# POWER_Management.net
KiCad netlist of a schematic drawn in Altium Designer
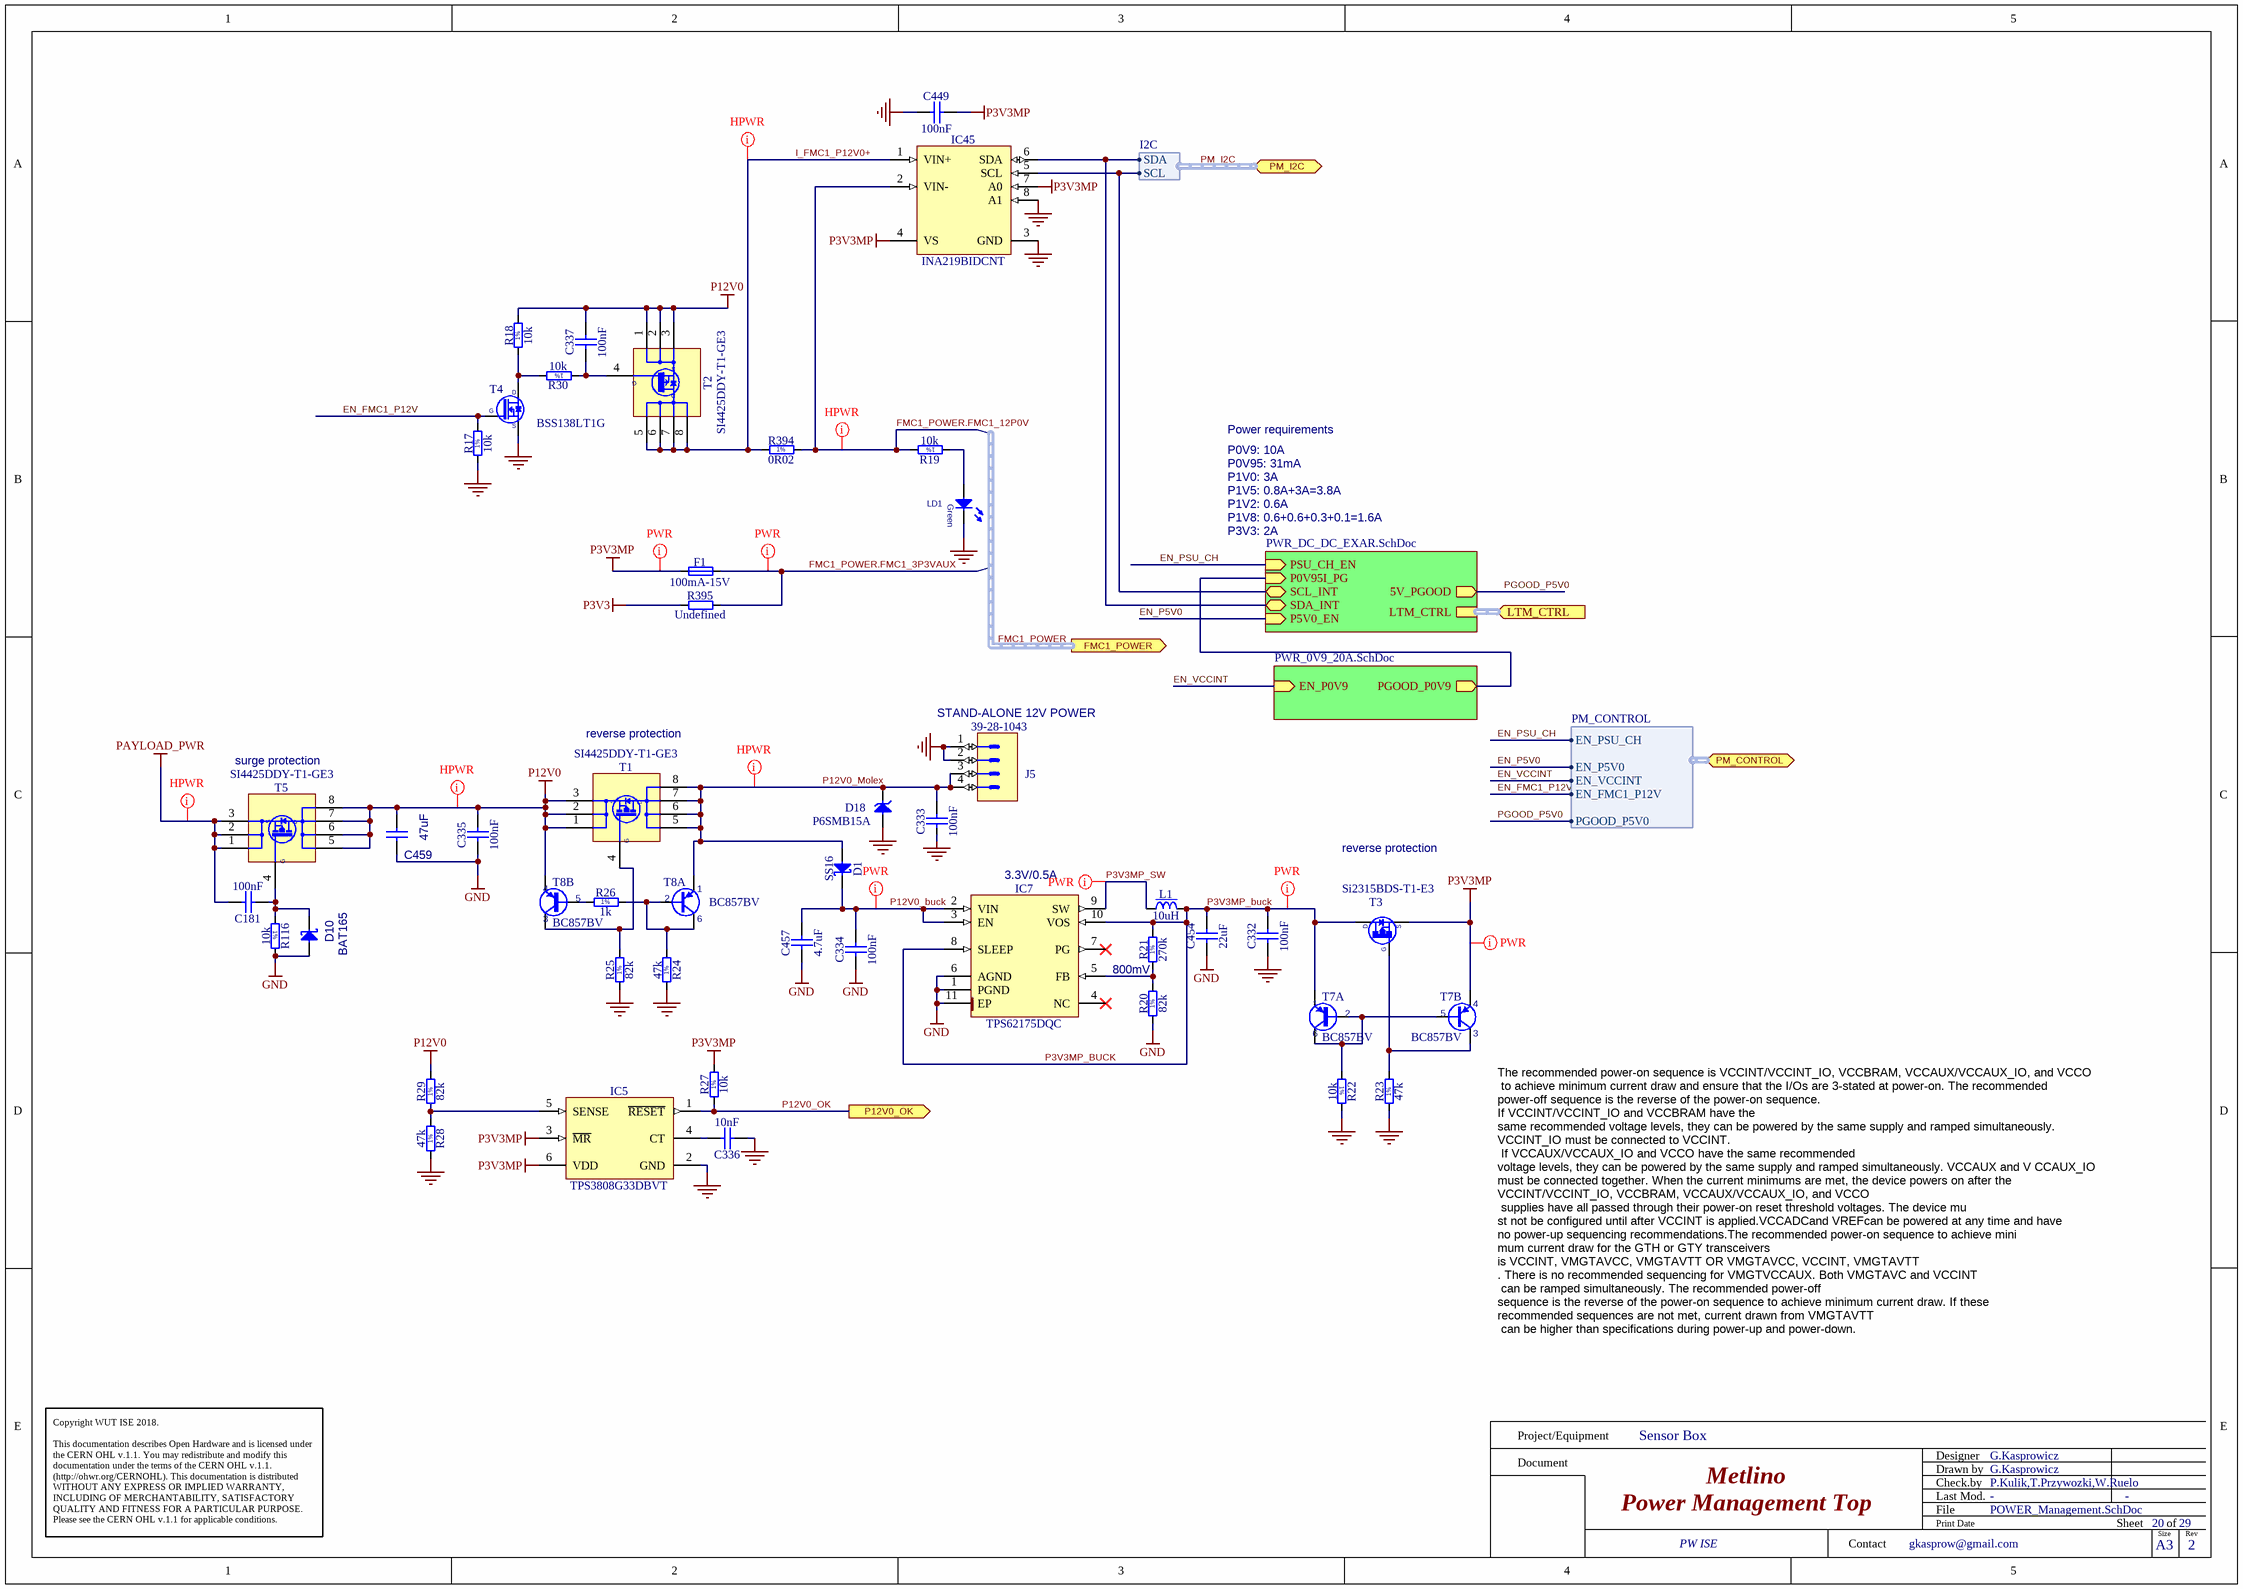
[diagram p0: POWER_Management.SchDoc]

(export (version "E")
  (design (tool "Eeschema 10.0.6"))
  (components
    (comp (ref "C181")
      (value "100nF")
      (footprint "CAPC1005X55N")
      (description "Non-polarised capacitor")
      (fields
        (field (name "MANUFACTURER PART NUMBER") "CC0402_100NF_16V_10%_X5R")
        (field (name "MANUFACTURER") "GENERIC")
        (field (name "AUTHOR") "CERN DEM JLC")
      )
      (libsource (lib "Capacitors") (part "Capacitor - non polarized"))
    )
    (comp (ref "C332")
      (value "100nF")
      (footprint "CAPC1005X55N")
      (description "Non-polarised capacitor")
      (fields
        (field (name "MANUFACTURER PART NUMBER") "CC0402_100NF_16V_10%_X5R")
        (field (name "MANUFACTURER") "GENERIC")
        (field (name "AUTHOR") "CERN DEM JLC")
      )
      (libsource (lib "Capacitors") (part "Capacitor - non polarized"))
    )
    (comp (ref "C333")
      (value "100nF")
      (footprint "CAPC1005X55N")
      (description "Non-polarised capacitor")
      (fields
        (field (name "MANUFACTURER PART NUMBER") "CC0402_100NF_16V_10%_X5R")
        (field (name "MANUFACTURER") "GENERIC")
        (field (name "AUTHOR") "CERN DEM JLC")
      )
      (libsource (lib "Capacitors") (part "Capacitor - non polarized"))
    )
    (comp (ref "C334")
      (value "100nF")
      (footprint "CAPC1005X55N")
      (description "Non-polarised capacitor")
      (fields
        (field (name "MANUFACTURER PART NUMBER") "CC0402_100NF_16V_10%_X5R")
        (field (name "MANUFACTURER") "GENERIC")
        (field (name "AUTHOR") "CERN DEM JLC")
      )
      (libsource (lib "Capacitors") (part "Capacitor - non polarized"))
    )
    (comp (ref "C335")
      (value "100nF")
      (footprint "CAPC1005X55N")
      (description "Non-polarised capacitor")
      (fields
        (field (name "MANUFACTURER PART NUMBER") "CC0402_100NF_16V_10%_X5R")
        (field (name "MANUFACTURER") "GENERIC")
        (field (name "AUTHOR") "CERN DEM JLC")
      )
      (libsource (lib "Capacitors") (part "Capacitor - non polarized"))
    )
    (comp (ref "C336")
      (value "10nF")
      (footprint "CAPC1005X55N")
      (description "Non-polarised capacitor")
      (fields
        (field (name "MANUFACTURER PART NUMBER") "CC0402_10NF_16V_10%_X7R")
        (field (name "MANUFACTURER") "GENERIC")
        (field (name "AUTHOR") "CERN DEM JLC")
      )
      (libsource (lib "Capacitors") (part "Capacitor - non polarized"))
    )
    (comp (ref "C337")
      (value "100nF")
      (footprint "CAPC1005X55N")
      (description "Non-polarised capacitor")
      (fields
        (field (name "MANUFACTURER PART NUMBER") "CC0402_100NF_16V_10%_X5R")
        (field (name "MANUFACTURER") "GENERIC")
        (field (name "AUTHOR") "CERN DEM JLC")
      )
      (libsource (lib "Capacitors") (part "Capacitor - non polarized"))
    )
    (comp (ref "C449")
      (value "100nF")
      (footprint "CAPC1005X55N")
      (description "Non-polarised capacitor")
      (fields
        (field (name "MANUFACTURER PART NUMBER") "CC0402_100NF_16V_10%_X5R")
        (field (name "MANUFACTURER") "GENERIC")
        (field (name "AUTHOR") "CERN DEM JLC")
      )
      (libsource (lib "Capacitors") (part "Capacitor - non polarized"))
    )
    (comp (ref "C454")
      (value "22uF")
      (footprint "CAPC2012X135N")
      (description "Non-polarised capacitor")
      (fields
        (field (name "MANUFACTURER PART NUMBER") "CC0805_22UF_16V_10%_X5R")
        (field (name "MANUFACTURER") "GENERIC")
        (field (name "AUTHOR") "CERN DEM JLC")
      )
      (libsource (lib "Capacitors") (part "Capacitor - non polarized"))
    )
    (comp (ref "C457")
      (value "4.7uF")
      (footprint "CAPC1709X95N")
      (description "Non-polarised capacitor")
      (fields
        (field (name "MANUFACTURER PART NUMBER") "CC0603_4.7UF_16V_10%_X5R")
        (field (name "MANUFACTURER") "GENERIC")
        (field (name "AUTHOR") "CERN DEM JLC")
      )
      (libsource (lib "Capacitors") (part "Capacitor - non polarized"))
    )
    (comp (ref "C459")
      (value "47uF")
      (footprint "CAPC3216X180N")
      (fields
        (field (name "$$NOTCOMMONPROPERTY_GENERAL PART NUMBER") "CC1206_47UF_25V_20%_X5R")
        (field (name "MANUFACTURER PART NUMBER") "C3216X5R1E476M160AC")
        (field (name "MANUFACTURER") "TDK")
      )
      (libsource (lib "") (part "root_1__*_1"))
    )
    (comp (ref "D1")
      (value "SS16")
      (footprint "DIOM5127X229N")
      (description "Schottky Diode")
      (fields
        (field (name "MANUFACTURER") "VISHAY GENERAL SEMICONDUCTOR")
        (field (name "VOLTAGE") "60V")
        (field (name "AUTHOR") "CERN DEM JLC")
      )
      (libsource (lib "ICs And Semiconductors") (part "Diode Schottky"))
    )
    (comp (ref "D10")
      (value "BAT165")
      (footprint "SOD2512X110N")
      (fields (field (name "MANUFACTURER") "INFINEON"))
      (libsource (lib "altium-import") (part "root_1__*"))
    )
    (comp (ref "D18")
      (value "P6SMB15A")
      (footprint "DIOM5436X261N")
      (description "Transient Voltage Suppressor Diode (Uni-Directional)")
      (fields
        (field (name "MANUFACTURER") "LITTELFUSE")
        (field (name "VOLTAGE") "15V")
        (field (name "AUTHOR") "CERN DEM JLC")
      )
      (libsource (lib "ICs And Semiconductors") (part "Diode TVS Uni-Directional"))
    )
    (comp (ref "F1")
      (value "100mA-15V")
      (footprint "FUSR_LITTELFUSE_0805L010")
      (description "Fuse")
      (fields
        (field (name "MANUFACTURER PART NUMBER") "0805L010YR")
        (field (name "MANUFACTURER") "LITTELFUSE")
        (field (name "AUTHOR") "CERN DEM JLC")
      )
      (libsource (lib "Eletro-mechanical") (part "Fuse"))
    )
    (comp (ref "IC5")
      (value "TPS3808G33DBVT")
      (footprint "SOT95P280X145-6N")
      (description "Low Quiescent Current, Programmable-Delay Supervisory Circuit")
      (fields (field (name "MANUFACTURER") "TEXAS INSTRUMENTS") (field (name "AUTHOR") "CERN DEM JLC"))
      (libsource (lib "ICs And Semiconductors") (part "TPS3808xxxDBV"))
    )
    (comp (ref "IC7")
      (value "TPS62175DQC")
      (footprint "SON50P200X300X80-11N-R94X250")
      (description "4.75-28VDC to 1-6VDC, 500mA Step-Down Converter With Sleep Mode")
      (fields (field (name "MANUFACTURER") "TEXAS INSTRUMENTS") (field (name "AUTHOR") "CERN DEM JMW"))
      (libsource (lib "ICs And Semiconductors") (part "TPS62175"))
    )
    (comp (ref "IC45")
      (value "INA219BIDCNT")
      (footprint "SOT65P280X145-8N")
      (description "Zero-Drift, Bi-Directional CURRENT/POWER MONITOR with I2C™ Interface")
      (fields (field (name "MANUFACTURER") "TEXAS INSTRUMENTS") (field (name "AUTHOR") "CERN DEM JLC"))
      (libsource (lib "ICs And Semiconductors") (part "INA219BIDCNT"))
    )
    (comp (ref "J5")
      (value "Mini-Fit Jr.™")
      (footprint "MOLEX_39-28-1043")
      (description "Connector 4 Male")
      (fields
        (field (name "MANUFACTURER PART NUMBER") "39-28-1043")
        (field (name "MANUFACTURER") "MOLEX")
        (field (name "PART NUMBER") "MOLEX_39-28-1043")
        (field (name "AUTHOR") "CERN DEM JLC")
      )
      (libsource (lib "Connectors") (part "Connector 4 Male"))
    )
    (comp (ref "L1")
      (value "10uH")
      (footprint "IND_MURATA-PS_8400")
      (description "Inductor With Core")
      (fields
        (field (name "MANUFACTURER PART NUMBER") "84103C")
        (field (name "MANUFACTURER") "MURATA POWER SOLUTIONS")
        (field (name "AUTHOR") "CERN DEM JLC")
      )
      (libsource (lib "Inductors & Transformers") (part "Inductor With Magnetic core"))
    )
    (comp (ref "LD1")
      (value "LED_OSRAM_LG L29K-G2J1-24-Z")
      (footprint "LED_OSRAM_LGL29K")
      (fields
        (field (name "MANUFACTURER PART NUMBER") "LG L29K-G2J1-24-Z")
        (field (name "MANUFACTURER") "OSRAM")
        (field (name "$$NOTCOMMONPROPERTY_AUTHOR") "CERN DEM JLC")
      )
      (libsource (lib "altium-import") (part "root_3__*"))
    )
    (comp (ref "R17")
      (value "10k")
      (footprint "RESC1005X40N")
      (description "Resistor - 1%")
      (fields
        (field (name "MANUFACTURER PART NUMBER") "R0402_10K_1%_0.0625W_100PPM")
        (field (name "MANUFACTURER") "GENERIC")
        (field (name "AUTHOR") "CERN DEM JLC")
      )
      (libsource (lib "Resistors") (part "Resistor - 1%"))
    )
    (comp (ref "R18")
      (value "10k")
      (footprint "RESC1005X40N")
      (description "Resistor - 1%")
      (fields
        (field (name "MANUFACTURER PART NUMBER") "R0402_10K_1%_0.0625W_100PPM")
        (field (name "MANUFACTURER") "GENERIC")
        (field (name "AUTHOR") "CERN DEM JLC")
      )
      (libsource (lib "Resistors") (part "Resistor - 1%"))
    )
    (comp (ref "R19")
      (value "10k")
      (footprint "RESC1005X40N")
      (description "Resistor - 1%")
      (fields
        (field (name "MANUFACTURER PART NUMBER") "R0402_10K_1%_0.0625W_100PPM")
        (field (name "MANUFACTURER") "GENERIC")
        (field (name "AUTHOR") "CERN DEM JLC")
      )
      (libsource (lib "Resistors") (part "Resistor - 1%"))
    )
    (comp (ref "R20")
      (value "82k")
      (footprint "RESC1005X40N")
      (description "Resistor - 1%")
      (fields
        (field (name "MANUFACTURER PART NUMBER") "R0402_82K_1%_0.0625W_100PPM")
        (field (name "MANUFACTURER") "GENERIC")
        (field (name "AUTHOR") "CERN DEM JLC")
      )
      (libsource (lib "Resistors") (part "Resistor - 1%"))
    )
    (comp (ref "R21")
      (value "270k")
      (footprint "RESC1005X40N")
      (description "Resistor - 1%")
      (fields
        (field (name "MANUFACTURER PART NUMBER") "R0402_270K_1%_0.0625W_100PPM")
        (field (name "MANUFACTURER") "GENERIC")
        (field (name "AUTHOR") "CERN DEM JLC")
      )
      (libsource (lib "Resistors") (part "Resistor - 1%"))
    )
    (comp (ref "R22")
      (value "10k")
      (footprint "RESC1005X40N")
      (description "Resistor - 1%")
      (fields
        (field (name "MANUFACTURER PART NUMBER") "R0402_10K_1%_0.0625W_100PPM")
        (field (name "MANUFACTURER") "GENERIC")
        (field (name "AUTHOR") "CERN DEM JLC")
      )
      (libsource (lib "Resistors") (part "Resistor - 1%"))
    )
    (comp (ref "R23")
      (value "47k")
      (footprint "RESC1005X40N")
      (description "Resistor - 1%")
      (fields
        (field (name "MANUFACTURER PART NUMBER") "R0402_47K_1%_0.0625W_100PPM")
        (field (name "MANUFACTURER") "GENERIC")
        (field (name "AUTHOR") "CERN DEM JLC")
      )
      (libsource (lib "Resistors") (part "Resistor - 1%"))
    )
    (comp (ref "R24")
      (value "47k")
      (footprint "RESC1005X40N")
      (description "Resistor - 1%")
      (fields
        (field (name "MANUFACTURER PART NUMBER") "R0402_47K_1%_0.0625W_100PPM")
        (field (name "MANUFACTURER") "GENERIC")
        (field (name "AUTHOR") "CERN DEM JLC")
      )
      (libsource (lib "Resistors") (part "Resistor - 1%"))
    )
    (comp (ref "R25")
      (value "82k")
      (footprint "RESC1005X40N")
      (description "Resistor - 1%")
      (fields
        (field (name "MANUFACTURER PART NUMBER") "R0402_82K_1%_0.0625W_100PPM")
        (field (name "MANUFACTURER") "GENERIC")
        (field (name "AUTHOR") "CERN DEM JLC")
      )
      (libsource (lib "Resistors") (part "Resistor - 1%"))
    )
    (comp (ref "R26")
      (value "1k")
      (footprint "RESC1005X40N")
      (description "Resistor - 1%")
      (fields
        (field (name "MANUFACTURER PART NUMBER") "R0402_1K_1%_0.0625W_100PPM")
        (field (name "MANUFACTURER") "GENERIC")
        (field (name "AUTHOR") "CERN DEM JLC")
      )
      (libsource (lib "Resistors") (part "Resistor - 1%"))
    )
    (comp (ref "R27")
      (value "10k")
      (footprint "RESC1005X40N")
      (description "Resistor - 1%")
      (fields
        (field (name "MANUFACTURER PART NUMBER") "R0402_10K_1%_0.0625W_100PPM")
        (field (name "MANUFACTURER") "GENERIC")
        (field (name "AUTHOR") "CERN DEM JLC")
      )
      (libsource (lib "Resistors") (part "Resistor - 1%"))
    )
    (comp (ref "R28")
      (value "47k")
      (footprint "RESC1005X40N")
      (description "Resistor - 1%")
      (fields
        (field (name "MANUFACTURER PART NUMBER") "R0402_47K_1%_0.0625W_100PPM")
        (field (name "MANUFACTURER") "GENERIC")
        (field (name "AUTHOR") "CERN DEM JLC")
      )
      (libsource (lib "Resistors") (part "Resistor - 1%"))
    )
    (comp (ref "R29")
      (value "82k")
      (footprint "RESC1005X40N")
      (description "Resistor - 1%")
      (fields
        (field (name "MANUFACTURER PART NUMBER") "R0402_82K_1%_0.0625W_100PPM")
        (field (name "MANUFACTURER") "GENERIC")
        (field (name "AUTHOR") "CERN DEM JLC")
      )
      (libsource (lib "Resistors") (part "Resistor - 1%"))
    )
    (comp (ref "R30")
      (value "10k")
      (footprint "RESC1005X40N")
      (description "Resistor - 1%")
      (fields
        (field (name "MANUFACTURER PART NUMBER") "R0402_10K_1%_0.0625W_100PPM")
        (field (name "MANUFACTURER") "GENERIC")
        (field (name "AUTHOR") "CERN DEM JLC")
      )
      (libsource (lib "Resistors") (part "Resistor - 1%"))
    )
    (comp (ref "R116")
      (value "10k")
      (footprint "RESC1005X40N")
      (description "Resistor - 1%")
      (fields
        (field (name "MANUFACTURER PART NUMBER") "R0402_10K_1%_0.0625W_100PPM")
        (field (name "MANUFACTURER") "GENERIC")
        (field (name "AUTHOR") "CERN DEM JLC")
      )
      (libsource (lib "Resistors") (part "Resistor - 1%"))
    )
    (comp (ref "R394")
      (value "0R02")
      (footprint "RESC_VISHAY_WSL2512_0R007-0R5")
      (description "Resistor - 1%")
      (fields
        (field (name "MANUFACTURER PART NUMBER") "WSL2512R0200FEA")
        (field (name "MANUFACTURER") "VISHAY DALE")
        (field (name "AUTHOR") "CERN DEM JLC")
      )
      (libsource (lib "Resistors") (part "Resistor - 1%"))
    )
    (comp (ref "R395")
      (value "Undefined")
      (footprint "RESC2012X60N")
      (description "Resistor")
      (fields
        (field (name "MANUFACTURER PART NUMBER") "R0805_NO-VALUE")
        (field (name "AUTHOR") "CERN DEM JLC")
      )
      (libsource (lib "Resistors") (part "Resistor"))
    )
    (comp (ref "T1")
      (value "SI4425DDY-T1-GE3")
      (footprint "SOIC127P600X175-8N")
      (description "-30V -19.7A P-Channel MOSFET")
      (fields (field (name "MANUFACTURER") "VISHAY SILICONIX") (field (name "AUTHOR") "CERN DEM MR"))
      (libsource (lib "ICs And Semiconductors") (part "SI4425DDY"))
    )
    (comp (ref "T2")
      (value "SI4425DDY-T1-GE3")
      (footprint "SOIC127P600X175-8N")
      (description "-30V -19.7A P-Channel MOSFET")
      (fields (field (name "MANUFACTURER") "VISHAY SILICONIX") (field (name "AUTHOR") "CERN DEM MR"))
      (libsource (lib "") (part "SI4425DDY_1"))
    )
    (comp (ref "T3")
      (value "Si2315BDS-T1-E3")
      (footprint "SOT95P237X112-3N")
      (description "P-CHANNEL MOSFET WITH DIODE")
      (fields (field (name "MANUFACTURER") "VISHAY SILICONIX") (field (name "AUTHOR") "CERN DEM JLC"))
      (libsource (lib "ICs And Semiconductors") (part "P-MOSFET-D 1G 2S 3D"))
    )
    (comp (ref "T4")
      (value "BSS138LT1G")
      (footprint "SOT95P240X110-3N")
      (description "N-CHANNEL MOSFET WITH DIODE")
      (fields (field (name "MANUFACTURER") "ON SEMICONDUCTOR") (field (name "AUTHOR") "CERN DEM JLC"))
      (libsource (lib "ICs And Semiconductors") (part "N-MOSFET-D 1G 2S 3D"))
    )
    (comp (ref "T5")
      (value "SI4425DDY-T1-GE3")
      (footprint "SOIC127P600X175-8N")
      (description "-30V -19.7A P-Channel MOSFET")
      (fields (field (name "MANUFACTURER") "VISHAY SILICONIX") (field (name "AUTHOR") "CERN DEM MR"))
      (libsource (lib "ICs And Semiconductors") (part "SI4425DDY"))
    )
    (comp (ref "T7")
      (value "BC857BV")
      (footprint "SOTFL50P160X60-6N")
      (description "45V, 100mA PNP General Purpose Double Transistor")
      (fields (field (name "MANUFACTURER") "NXP SEMICONDUCTORS") (field (name "AUTHOR") "CERN DEM JLC"))
      (libsource (lib "ICs And Semiconductors") (part "BC857BV"))
    )
    (comp (ref "T8")
      (value "BC857BV")
      (footprint "SOTFL50P160X60-6N")
      (description "45V, 100mA PNP General Purpose Double Transistor")
      (fields (field (name "MANUFACTURER") "NXP SEMICONDUCTORS") (field (name "AUTHOR") "CERN DEM JLC"))
      (libsource (lib "") (part "BC857BV_1"))
    )
  )
  (nets
    (net (code "5") (name "/EN_FMC1_P12V") (class "Default")
      (node (ref "R17") (pin "2") (pinfunction "2_2") (pintype "passive"))
      (node (ref "T4") (pin "1") (pinfunction "G_1") (pintype "passive"))
    )
    (net (code "9") (name "/FMC1_POWER.FMC1_3P3VAUX") (class "Default")
      (node (ref "F1") (pin "2") (pinfunction "2_2") (pintype "passive"))
      (node (ref "R395") (pin "2") (pinfunction "2_2") (pintype "passive"))
    )
    (net (code "10") (name "/FMC1_POWER.FMC1_12P0V") (class "Default")
      (node (ref "IC45") (pin "2") (pinfunction "VIN-_2") (pintype "input"))
      (node (ref "R19") (pin "2") (pinfunction "2_2") (pintype "passive"))
      (node (ref "R394") (pin "2") (pinfunction "2_2") (pintype "passive"))
    )
    (net (code "11") (name "/I_FMC1_P12V0+") (class "Default")
      (node (ref "IC45") (pin "1") (pinfunction "VIN+_1") (pintype "input"))
      (node (ref "R394") (pin "1") (pinfunction "1_1") (pintype "passive"))
      (node (ref "T2") (pin "5") (pinfunction "D_5") (pintype "passive"))
      (node (ref "T2") (pin "6") (pinfunction "D_6") (pintype "passive"))
      (node (ref "T2") (pin "7") (pinfunction "D_7") (pintype "passive"))
      (node (ref "T2") (pin "8") (pinfunction "D_8") (pintype "passive"))
    )
    (net (code "13") (name "/P3V3MP_BUCK") (class "Default")
      (node (ref "C332") (pin "2") (pinfunction "2_2") (pintype "passive"))
      (node (ref "C454") (pin "2") (pinfunction "2_2") (pintype "passive"))
      (node (ref "IC7") (pin "10") (pinfunction "VOS_10") (pintype "input"))
      (node (ref "IC7") (pin "8") (pinfunction "SLEEP_8") (pintype "input"))
      (node (ref "L1") (pin "2") (pinfunction "2_2") (pintype "passive"))
      (node (ref "R21") (pin "2") (pinfunction "2_2") (pintype "passive"))
      (node (ref "T3") (pin "3") (pinfunction "D_3") (pintype "passive"))
      (node (ref "T7") (pin "1") (pinfunction "E_1") (pintype "passive"))
    )
    (net (code "14") (name "/P3V3MP_SW") (class "Default")
      (node (ref "IC7") (pin "9") (pinfunction "SW_9") (pintype "output"))
      (node (ref "L1") (pin "1") (pinfunction "1_1") (pintype "passive"))
    )
    (net (code "15") (name "/P12V0_Molex") (class "Default")
      (node (ref "C333") (pin "2") (pinfunction "2_2") (pintype "passive"))
      (node (ref "D1") (pin "2") (pinfunction "A_2") (pintype "passive"))
      (node (ref "D18") (pin "1") (pinfunction "C_1") (pintype "passive"))
      (node (ref "J5") (pin "3") (pinfunction "3_3") (pintype "bidirectional"))
      (node (ref "J5") (pin "4") (pinfunction "4_4") (pintype "bidirectional"))
      (node (ref "T1") (pin "5") (pinfunction "D_5") (pintype "passive"))
      (node (ref "T1") (pin "6") (pinfunction "D_6") (pintype "passive"))
      (node (ref "T1") (pin "7") (pinfunction "D_7") (pintype "passive"))
      (node (ref "T1") (pin "8") (pinfunction "D_8") (pintype "passive"))
      (node (ref "T8") (pin "1") (pinfunction "E_1") (pintype "passive"))
    )
    (net (code "16") (name "/P12V0_OK") (class "Default")
      (node (ref "IC5") (pin "1") (pinfunction "~{RESET}_1") (pintype "output"))
      (node (ref "R27") (pin "1") (pinfunction "1_1") (pintype "passive"))
    )
    (net (code "17") (name "/P12V0_buck") (class "Default")
      (node (ref "C334") (pin "2") (pinfunction "2_2") (pintype "passive"))
      (node (ref "C457") (pin "2") (pinfunction "2_2") (pintype "passive"))
      (node (ref "D1") (pin "1") (pinfunction "C_1") (pintype "passive"))
      (node (ref "IC7") (pin "2") (pinfunction "VIN_2") (pintype "input"))
      (node (ref "IC7") (pin "3") (pinfunction "EN_3") (pintype "input"))
    )
    (net (code "21") (name "/SCL_INT") (class "Default")
      (node (ref "IC45") (pin "5") (pinfunction "SCL_5") (pintype "input"))
    )
    (net (code "22") (name "/SDA_INT") (class "Default")
      (node (ref "IC45") (pin "6") (pinfunction "SDA_6") (pintype "bidirectional"))
    )
    (net (code "25") (name "GND") (class "Default")
      (node (ref "C332") (pin "1") (pinfunction "1_1") (pintype "passive"))
      (node (ref "C333") (pin "1") (pinfunction "1_1") (pintype "passive"))
      (node (ref "C334") (pin "1") (pinfunction "1_1") (pintype "passive"))
      (node (ref "C335") (pin "1") (pinfunction "1_1") (pintype "passive"))
      (node (ref "C336") (pin "1") (pinfunction "1_1") (pintype "passive"))
      (node (ref "C449") (pin "1") (pinfunction "1_1") (pintype "passive"))
      (node (ref "C454") (pin "1") (pinfunction "1_1") (pintype "passive"))
      (node (ref "C457") (pin "1") (pinfunction "1_1") (pintype "passive"))
      (node (ref "C459") (pin "1") (pinfunction "1_1") (pintype "passive"))
      (node (ref "D10") (pin "2") (pinfunction "A_2") (pintype "passive"))
      (node (ref "D18") (pin "2") (pinfunction "A_2") (pintype "passive"))
      (node (ref "IC45") (pin "3") (pinfunction "GND_3") (pintype "power_in"))
      (node (ref "IC45") (pin "8") (pinfunction "A1_8") (pintype "input"))
      (node (ref "IC5") (pin "2") (pinfunction "GND_2") (pintype "power_in"))
      (node (ref "IC7") (pin "1") (pinfunction "PGND_1") (pintype "power_in"))
      (node (ref "IC7") (pin "11") (pinfunction "EP_11") (pintype "power_in"))
      (node (ref "IC7") (pin "6") (pinfunction "AGND_6") (pintype "power_in"))
      (node (ref "J5") (pin "1") (pinfunction "1_1") (pintype "bidirectional"))
      (node (ref "J5") (pin "2") (pinfunction "2_2") (pintype "bidirectional"))
      (node (ref "LD1") (pin "1") (pinfunction "C_1") (pintype "passive"))
      (node (ref "R116") (pin "2") (pinfunction "2_2") (pintype "passive"))
      (node (ref "R17") (pin "1") (pinfunction "1_1") (pintype "passive"))
      (node (ref "R20") (pin "1") (pinfunction "1_1") (pintype "passive"))
      (node (ref "R22") (pin "2") (pinfunction "2_2") (pintype "passive"))
      (node (ref "R23") (pin "1") (pinfunction "1_1") (pintype "passive"))
      (node (ref "R24") (pin "1") (pinfunction "1_1") (pintype "passive"))
      (node (ref "R25") (pin "1") (pinfunction "1_1") (pintype "passive"))
      (node (ref "R28") (pin "1") (pinfunction "1_1") (pintype "passive"))
      (node (ref "T4") (pin "2") (pinfunction "S_2") (pintype "passive"))
    )
    (net (code "26") (name "Net-(C337-Pad1)") (class "Default")
      (node (ref "C337") (pin "1") (pinfunction "1_1") (pintype "passive"))
      (node (ref "R30") (pin "1") (pinfunction "1_1") (pintype "passive"))
      (node (ref "T2") (pin "4") (pinfunction "S_4") (pintype "passive"))
    )
    (net (code "27") (name "Net-(D10-C)") (class "Default")
      (node (ref "C181") (pin "1") (pinfunction "1_1") (pintype "passive"))
      (node (ref "D10") (pin "1") (pinfunction "C_1") (pintype "passive"))
      (node (ref "R116") (pin "1") (pinfunction "1_1") (pintype "passive"))
      (node (ref "T5") (pin "4") (pinfunction "S_4") (pintype "passive"))
    )
    (net (code "28") (name "Net-(IC5-CT)") (class "Default")
      (node (ref "C336") (pin "2") (pinfunction "2_2") (pintype "passive"))
      (node (ref "IC5") (pin "4") (pinfunction "CT_4") (pintype "passive"))
    )
    (net (code "29") (name "Net-(IC5-SENSE)") (class "Default")
      (node (ref "IC5") (pin "5") (pinfunction "SENSE_5") (pintype "input"))
      (node (ref "R28") (pin "2") (pinfunction "2_2") (pintype "passive"))
      (node (ref "R29") (pin "1") (pinfunction "1_1") (pintype "passive"))
    )
    (net (code "30") (name "Net-(IC7-FB)") (class "Default")
      (node (ref "IC7") (pin "5") (pinfunction "FB_5") (pintype "input"))
      (node (ref "R20") (pin "2") (pinfunction "2_2") (pintype "passive"))
      (node (ref "R21") (pin "1") (pinfunction "1_1") (pintype "passive"))
    )
    (net (code "31") (name "Net-(LD1-A)") (class "Default")
      (node (ref "LD1") (pin "2") (pinfunction "A_2") (pintype "passive"))
      (node (ref "R19") (pin "1") (pinfunction "1_1") (pintype "passive"))
    )
    (net (code "32") (name "Net-(T3-G)") (class "Default")
      (node (ref "R23") (pin "2") (pinfunction "2_2") (pintype "passive"))
      (node (ref "T3") (pin "1") (pinfunction "G_1") (pintype "passive"))
      (node (ref "T7") (pin "3") (pinfunction "C_3") (pintype "passive"))
    )
    (net (code "33") (name "Net-(T4-D)") (class "Default")
      (node (ref "R18") (pin "1") (pinfunction "1_1") (pintype "passive"))
      (node (ref "R30") (pin "2") (pinfunction "2_2") (pintype "passive"))
      (node (ref "T4") (pin "3") (pinfunction "D_3") (pintype "passive"))
    )
    (net (code "34") (name "Net-(T7A-B)") (class "Default")
      (node (ref "R22") (pin "1") (pinfunction "1_1") (pintype "passive"))
      (node (ref "T7") (pin "2") (pinfunction "B_2") (pintype "passive"))
      (node (ref "T7") (pin "5") (pinfunction "B_5") (pintype "passive"))
      (node (ref "T7") (pin "6") (pinfunction "C_6") (pintype "passive"))
    )
    (net (code "35") (name "Net-(T8A-B)") (class "Default")
      (node (ref "R24") (pin "2") (pinfunction "2_2") (pintype "passive"))
      (node (ref "R26") (pin "2") (pinfunction "2_2") (pintype "passive"))
      (node (ref "T8") (pin "2") (pinfunction "B_2") (pintype "passive"))
      (node (ref "T8") (pin "6") (pinfunction "C_6") (pintype "passive"))
    )
    (net (code "36") (name "Net-(T8B-B)") (class "Default")
      (node (ref "R26") (pin "1") (pinfunction "1_1") (pintype "passive"))
      (node (ref "T8") (pin "5") (pinfunction "B_5") (pintype "passive"))
    )
    (net (code "37") (name "Net-(T8B-C)") (class "Default")
      (node (ref "R25") (pin "2") (pinfunction "2_2") (pintype "passive"))
      (node (ref "T1") (pin "4") (pinfunction "S_4") (pintype "passive"))
      (node (ref "T8") (pin "3") (pinfunction "C_3") (pintype "passive"))
    )
    (net (code "38") (name "P3V3") (class "Default")
      (node (ref "R395") (pin "1") (pinfunction "1_1") (pintype "passive"))
    )
    (net (code "39") (name "P3V3MP") (class "Default")
      (node (ref "C449") (pin "2") (pinfunction "2_2") (pintype "passive"))
      (node (ref "F1") (pin "1") (pinfunction "1_1") (pintype "passive"))
      (node (ref "IC45") (pin "4") (pinfunction "VS_4") (pintype "power_in"))
      (node (ref "IC45") (pin "7") (pinfunction "A0_7") (pintype "input"))
      (node (ref "IC5") (pin "3") (pinfunction "~{MR}_3") (pintype "input"))
      (node (ref "IC5") (pin "6") (pinfunction "VDD_6") (pintype "power_in"))
      (node (ref "R27") (pin "2") (pinfunction "2_2") (pintype "passive"))
      (node (ref "T3") (pin "2") (pinfunction "S_2") (pintype "passive"))
      (node (ref "T7") (pin "4") (pinfunction "E_4") (pintype "passive"))
    )
    (net (code "40") (name "P12V0") (class "Default")
      (node (ref "C335") (pin "2") (pinfunction "2_2") (pintype "passive"))
      (node (ref "C337") (pin "2") (pinfunction "2_2") (pintype "passive"))
      (node (ref "C459") (pin "2") (pinfunction "2_2") (pintype "passive"))
      (node (ref "R18") (pin "2") (pinfunction "2_2") (pintype "passive"))
      (node (ref "R29") (pin "2") (pinfunction "2_2") (pintype "passive"))
      (node (ref "T1") (pin "1") (pinfunction "S_1") (pintype "passive"))
      (node (ref "T1") (pin "2") (pinfunction "S_2") (pintype "passive"))
      (node (ref "T1") (pin "3") (pinfunction "S_3") (pintype "passive"))
      (node (ref "T2") (pin "1") (pinfunction "S_1") (pintype "passive"))
      (node (ref "T2") (pin "2") (pinfunction "S_2") (pintype "passive"))
      (node (ref "T2") (pin "3") (pinfunction "S_3") (pintype "passive"))
      (node (ref "T5") (pin "5") (pinfunction "D_5") (pintype "passive"))
      (node (ref "T5") (pin "6") (pinfunction "D_6") (pintype "passive"))
      (node (ref "T5") (pin "7") (pinfunction "D_7") (pintype "passive"))
      (node (ref "T5") (pin "8") (pinfunction "D_8") (pintype "passive"))
      (node (ref "T8") (pin "4") (pinfunction "E_4") (pintype "passive"))
    )
    (net (code "41") (name "PAYLOAD_PWR") (class "Default")
      (node (ref "C181") (pin "2") (pinfunction "2_2") (pintype "passive"))
      (node (ref "T5") (pin "1") (pinfunction "S_1") (pintype "passive"))
      (node (ref "T5") (pin "2") (pinfunction "S_2") (pintype "passive"))
      (node (ref "T5") (pin "3") (pinfunction "S_3") (pintype "passive"))
    )
    (net (code "42") (name "unconnected-(IC7-NC-Pad4)") (class "Default")
      (node (ref "IC7") (pin "4") (pinfunction "NC_4") (pintype "passive+no_connect"))
    )
    (net (code "43") (name "unconnected-(IC7-PG-Pad7)") (class "Default")
      (node (ref "IC7") (pin "7") (pinfunction "PG_7") (pintype "output+no_connect"))
    )
  )
)
